# asdr.net
KiCad netlist of a schematic drawn in EAGLE
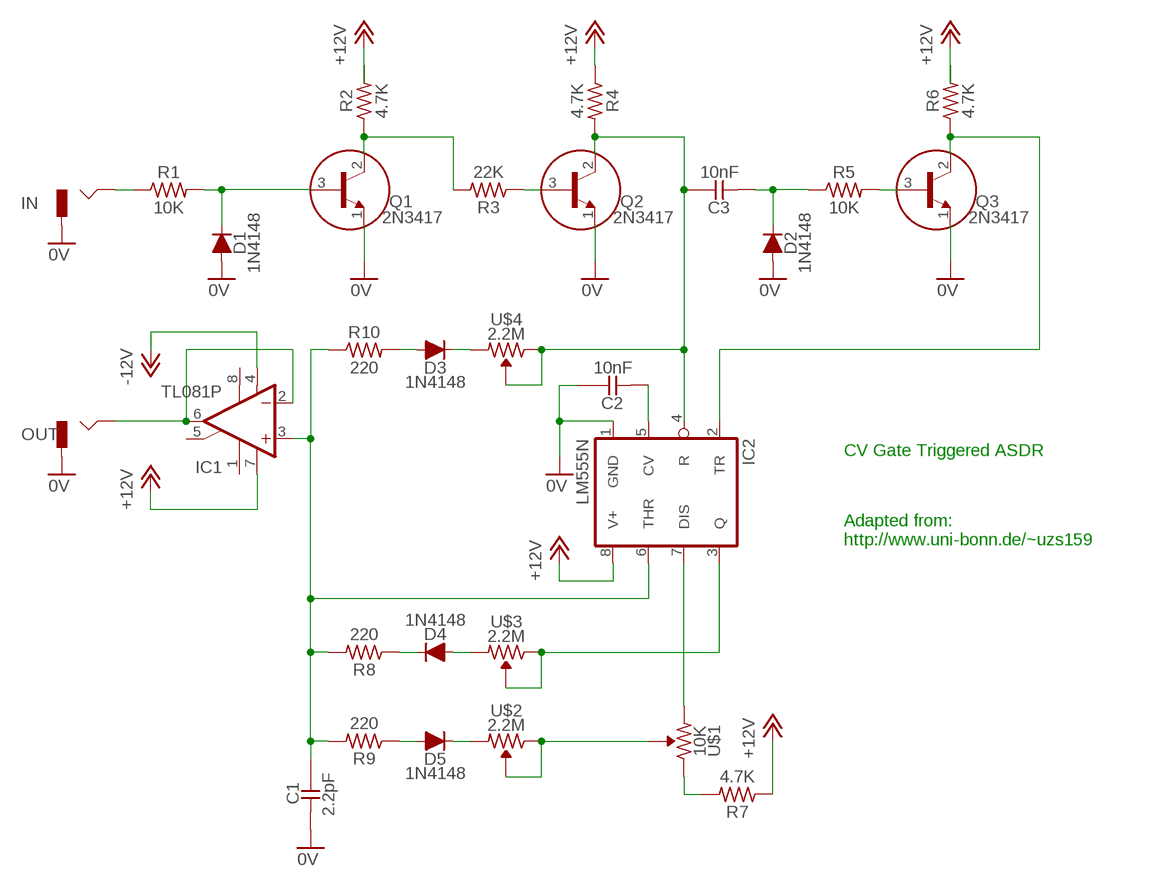
[diagram p0: schematic, sheet 1]

(export (version "E")
  (design (tool "Eeschema 10.0.6"))
  (components
    (comp (ref "C1")
      (value "2.2pF")
      (footprint "eagle-import:C025-024X044")
      (libsource (lib "eagle-import") (part "CC-US025-024X044"))
    )
    (comp (ref "C2")
      (value "10nF")
      (footprint "eagle-import:C025-024X044")
      (libsource (lib "eagle-import") (part "CC-US025-024X044"))
    )
    (comp (ref "C3")
      (value "10nF")
      (footprint "eagle-import:C025-024X044")
      (libsource (lib "eagle-import") (part "CC-US025-024X044"))
    )
    (comp (ref "D1")
      (value "1N4148")
      (footprint "eagle-import:DO35-7")
      (libsource (lib "eagle-import") (part "1N4148"))
    )
    (comp (ref "D2")
      (value "1N4148")
      (footprint "eagle-import:DO35-7")
      (libsource (lib "eagle-import") (part "1N4148"))
    )
    (comp (ref "D3")
      (value "1N4148")
      (footprint "eagle-import:DO35-7")
      (libsource (lib "eagle-import") (part "1N4148"))
    )
    (comp (ref "D4")
      (value "1N4148")
      (footprint "eagle-import:DO35-7")
      (libsource (lib "eagle-import") (part "1N4148"))
    )
    (comp (ref "D5")
      (value "1N4148")
      (footprint "eagle-import:DO35-7")
      (libsource (lib "eagle-import") (part "1N4148"))
    )
    (comp (ref "IC1")
      (value "TL081P")
      (footprint "eagle-import:DIL08")
      (libsource (lib "eagle-import") (part "TL081P"))
    )
    (comp (ref "IC2")
      (value "LM555N")
      (footprint "eagle-import:DIL08")
      (libsource (lib "eagle-import") (part "555NLM"))
    )
    (comp (ref "IN")
      (value "JACK-M")
      (footprint "eagle-import:JACK-M")
      (libsource (lib "eagle-import") (part "JACK-M"))
    )
    (comp (ref "OUT")
      (value "JACK-M")
      (footprint "eagle-import:JACK-M")
      (libsource (lib "eagle-import") (part "JACK-M"))
    )
    (comp (ref "Q1")
      (value "2N3417")
      (footprint "eagle-import:TO92")
      (libsource (lib "eagle-import") (part "2N3417"))
    )
    (comp (ref "Q2")
      (value "2N3417")
      (footprint "eagle-import:TO92")
      (libsource (lib "eagle-import") (part "2N3417"))
    )
    (comp (ref "Q3")
      (value "2N3417")
      (footprint "eagle-import:TO92")
      (libsource (lib "eagle-import") (part "2N3417"))
    )
    (comp (ref "R1")
      (value "10K")
      (footprint "eagle-import:0309_10")
      (libsource (lib "eagle-import") (part "R0309/10"))
    )
    (comp (ref "R2")
      (value "4.7K")
      (footprint "eagle-import:0309_10")
      (libsource (lib "eagle-import") (part "R0309/10"))
    )
    (comp (ref "R3")
      (value "22K")
      (footprint "eagle-import:0309_10")
      (libsource (lib "eagle-import") (part "R0309/10"))
    )
    (comp (ref "R4")
      (value "4.7K")
      (footprint "eagle-import:0309_10")
      (libsource (lib "eagle-import") (part "R0309/10"))
    )
    (comp (ref "R5")
      (value "10K")
      (footprint "eagle-import:0309_10")
      (libsource (lib "eagle-import") (part "R0309/10"))
    )
    (comp (ref "R6")
      (value "4.7K")
      (footprint "eagle-import:0309_10")
      (libsource (lib "eagle-import") (part "R0309/10"))
    )
    (comp (ref "R7")
      (value "4.7K")
      (footprint "eagle-import:0309_10")
      (libsource (lib "eagle-import") (part "R0309/10"))
    )
    (comp (ref "R8")
      (value "220")
      (footprint "eagle-import:0309_10")
      (libsource (lib "eagle-import") (part "R0309/10"))
    )
    (comp (ref "R9")
      (value "220")
      (footprint "eagle-import:0309_10")
      (libsource (lib "eagle-import") (part "R0309/10"))
    )
    (comp (ref "R10")
      (value "220")
      (footprint "eagle-import:0309_10")
      (libsource (lib "eagle-import") (part "R0309/10"))
    )
    (comp (ref "U$1")
      (value "10K")
      (footprint "eagle-import:R-VAR")
      (libsource (lib "eagle-import") (part "R-VAR"))
    )
    (comp (ref "U$2")
      (value "2.2M")
      (footprint "eagle-import:R-VAR")
      (libsource (lib "eagle-import") (part "R-VAR"))
    )
    (comp (ref "U$3")
      (value "2.2M")
      (footprint "eagle-import:R-VAR")
      (libsource (lib "eagle-import") (part "R-VAR"))
    )
    (comp (ref "U$4")
      (value "2.2M")
      (footprint "eagle-import:R-VAR")
      (libsource (lib "eagle-import") (part "R-VAR"))
    )
  )
  (nets
    (net (code "1") (name "+12V") (class "Default")
      (node (ref "IC1") (pin "7") (pinfunction "V+_7") (pintype "power_in"))
      (node (ref "IC2") (pin "8") (pinfunction "V+_8") (pintype "power_in"))
      (node (ref "R4") (pin "1") (pinfunction "1_1") (pintype "passive"))
      (node (ref "R7") (pin "1") (pinfunction "1_1") (pintype "passive"))
    )
    (net (code "2") (name "-12V") (class "Default")
      (node (ref "IC1") (pin "4") (pinfunction "V-_4") (pintype "power_in"))
    )
    (net (code "3") (name "0V") (class "Default")
      (node (ref "C1") (pin "2") (pinfunction "2_2") (pintype "passive"))
      (node (ref "C2") (pin "1") (pinfunction "1_1") (pintype "passive"))
      (node (ref "D1") (pin "A") (pinfunction "A_A") (pintype "passive"))
      (node (ref "D2") (pin "A") (pinfunction "A_A") (pintype "passive"))
      (node (ref "IC2") (pin "1") (pinfunction "GND_1") (pintype "power_in"))
      (node (ref "IN") (pin "GND") (pinfunction "GND_GND") (pintype "bidirectional"))
      (node (ref "OUT") (pin "GND") (pinfunction "GND_GND") (pintype "bidirectional"))
      (node (ref "Q1") (pin "1") (pinfunction "E_1") (pintype "passive"))
      (node (ref "Q2") (pin "1") (pinfunction "E_1") (pintype "passive"))
      (node (ref "Q3") (pin "1") (pinfunction "E_1") (pintype "passive"))
    )
    (net (code "4") (name "Net-(C3-Pad2)") (class "Default")
      (node (ref "C3") (pin "2") (pinfunction "2_2") (pintype "passive"))
      (node (ref "D2") (pin "C") (pinfunction "C_C") (pintype "passive"))
      (node (ref "R5") (pin "1") (pinfunction "1_1") (pintype "passive"))
    )
    (net (code "5") (name "Net-(D3-PadA)") (class "Default")
      (node (ref "D3") (pin "A") (pinfunction "A_A") (pintype "passive"))
      (node (ref "R10") (pin "2") (pinfunction "2_2") (pintype "passive"))
    )
    (net (code "6") (name "Net-(D4-PadC)") (class "Default")
      (node (ref "D4") (pin "C") (pinfunction "C_C") (pintype "passive"))
      (node (ref "R8") (pin "1") (pinfunction "1_1") (pintype "passive"))
    )
    (net (code "7") (name "Net-(D5-PadA)") (class "Default")
      (node (ref "D5") (pin "A") (pinfunction "A_A") (pintype "passive"))
      (node (ref "R9") (pin "1") (pinfunction "1_1") (pintype "passive"))
    )
    (net (code "8") (name "Net-(IC1-+IN)") (class "Default")
      (node (ref "C1") (pin "1") (pinfunction "1_1") (pintype "passive"))
      (node (ref "IC1") (pin "3") (pinfunction "+IN_3") (pintype "input"))
      (node (ref "IC2") (pin "6") (pinfunction "THR_6") (pintype "input"))
      (node (ref "R10") (pin "1") (pinfunction "1_1") (pintype "passive"))
      (node (ref "R8") (pin "2") (pinfunction "2_2") (pintype "passive"))
      (node (ref "R9") (pin "2") (pinfunction "2_2") (pintype "passive"))
    )
    (net (code "9") (name "Net-(IC1--IN)") (class "Default")
      (node (ref "IC1") (pin "2") (pinfunction "-IN_2") (pintype "input"))
      (node (ref "IC1") (pin "6") (pinfunction "OUT_6") (pintype "output"))
      (node (ref "OUT") (pin "HOT") (pinfunction "HOT_HOT") (pintype "bidirectional"))
    )
    (net (code "10") (name "Net-(IC2-CV)") (class "Default")
      (node (ref "C2") (pin "2") (pinfunction "2_2") (pintype "passive"))
      (node (ref "IC2") (pin "5") (pinfunction "CV_5") (pintype "input"))
    )
    (net (code "11") (name "Net-(IC2-DIS)") (class "Default")
      (node (ref "IC2") (pin "7") (pinfunction "DIS_7") (pintype "input"))
      (node (ref "U$1") (pin "R2") (pinfunction "2_R2") (pintype "passive"))
    )
    (net (code "12") (name "Net-(IC2-Q)") (class "Default")
      (node (ref "IC2") (pin "3") (pinfunction "Q_3") (pintype "output"))
      (node (ref "U$3") (pin "R1") (pinfunction "1_R1") (pintype "passive"))
      (node (ref "U$3") (pin "VAR") (pinfunction "P$1_VAR") (pintype "passive"))
    )
    (net (code "13") (name "Net-(IC2-R)") (class "Default")
      (node (ref "C3") (pin "1") (pinfunction "1_1") (pintype "passive"))
      (node (ref "IC2") (pin "4") (pinfunction "R_4") (pintype "input"))
      (node (ref "Q2") (pin "2") (pinfunction "C_2") (pintype "passive"))
      (node (ref "R4") (pin "2") (pinfunction "2_2") (pintype "passive"))
      (node (ref "U$4") (pin "R1") (pinfunction "1_R1") (pintype "passive"))
      (node (ref "U$4") (pin "VAR") (pinfunction "P$1_VAR") (pintype "passive"))
    )
    (net (code "14") (name "Net-(IC2-TR)") (class "Default")
      (node (ref "IC2") (pin "2") (pinfunction "TR_2") (pintype "input"))
      (node (ref "Q3") (pin "2") (pinfunction "C_2") (pintype "passive"))
      (node (ref "R6") (pin "1") (pinfunction "1_1") (pintype "passive"))
    )
    (net (code "15") (name "Net-(IN-PadHOT)") (class "Default")
      (node (ref "IN") (pin "HOT") (pinfunction "HOT_HOT") (pintype "bidirectional"))
      (node (ref "R1") (pin "1") (pinfunction "1_1") (pintype "passive"))
    )
    (net (code "16") (name "Net-(Q1-B)") (class "Default")
      (node (ref "D1") (pin "C") (pinfunction "C_C") (pintype "passive"))
      (node (ref "Q1") (pin "3") (pinfunction "B_3") (pintype "passive"))
      (node (ref "R1") (pin "2") (pinfunction "2_2") (pintype "passive"))
    )
    (net (code "17") (name "Net-(Q1-C)") (class "Default")
      (node (ref "Q1") (pin "2") (pinfunction "C_2") (pintype "passive"))
      (node (ref "R2") (pin "1") (pinfunction "1_1") (pintype "passive"))
      (node (ref "R3") (pin "2") (pinfunction "2_2") (pintype "passive"))
    )
    (net (code "18") (name "Net-(Q2-B)") (class "Default")
      (node (ref "Q2") (pin "3") (pinfunction "B_3") (pintype "passive"))
      (node (ref "R3") (pin "1") (pinfunction "1_1") (pintype "passive"))
    )
    (net (code "19") (name "Net-(Q3-B)") (class "Default")
      (node (ref "Q3") (pin "3") (pinfunction "B_3") (pintype "passive"))
      (node (ref "R5") (pin "2") (pinfunction "2_2") (pintype "passive"))
    )
    (net (code "20") (name "Net-(U$1-1)") (class "Default")
      (node (ref "R7") (pin "2") (pinfunction "2_2") (pintype "passive"))
      (node (ref "U$1") (pin "R1") (pinfunction "1_R1") (pintype "passive"))
    )
    (net (code "21") (name "Net-(U$1-P$1)") (class "Default")
      (node (ref "U$1") (pin "VAR") (pinfunction "P$1_VAR") (pintype "passive"))
      (node (ref "U$2") (pin "R1") (pinfunction "1_R1") (pintype "passive"))
      (node (ref "U$2") (pin "VAR") (pinfunction "P$1_VAR") (pintype "passive"))
    )
    (net (code "22") (name "Net-(U$2-2)") (class "Default")
      (node (ref "D5") (pin "C") (pinfunction "C_C") (pintype "passive"))
      (node (ref "U$2") (pin "R2") (pinfunction "2_R2") (pintype "passive"))
    )
    (net (code "23") (name "Net-(U$3-2)") (class "Default")
      (node (ref "D4") (pin "A") (pinfunction "A_A") (pintype "passive"))
      (node (ref "U$3") (pin "R2") (pinfunction "2_R2") (pintype "passive"))
    )
    (net (code "24") (name "Net-(U$4-2)") (class "Default")
      (node (ref "D3") (pin "C") (pinfunction "C_C") (pintype "passive"))
      (node (ref "U$4") (pin "R2") (pinfunction "2_R2") (pintype "passive"))
    )
    (net (code "25") (name "unconnected-(IC1-ON1-Pad1)") (class "Default")
      (node (ref "IC1") (pin "1") (pinfunction "ON1_1") (pintype "passive"))
    )
    (net (code "26") (name "unconnected-(IC1-ON2-Pad5)") (class "Default")
      (node (ref "IC1") (pin "5") (pinfunction "ON2_5") (pintype "passive"))
    )
    (net (code "27") (name "unconnected-(IC1-OPT-Pad8)") (class "Default")
      (node (ref "IC1") (pin "8") (pinfunction "OPT_8") (pintype "passive"))
    )
    (net (code "28") (name "unconnected-(R2-Pad2)") (class "Default")
      (node (ref "R2") (pin "2") (pinfunction "2_2") (pintype "passive"))
    )
    (net (code "29") (name "unconnected-(R6-Pad2)") (class "Default")
      (node (ref "R6") (pin "2") (pinfunction "2_2") (pintype "passive"))
    )
  )
)
